# scraptcha.net
KiCad netlist of a schematic drawn in EAGLE
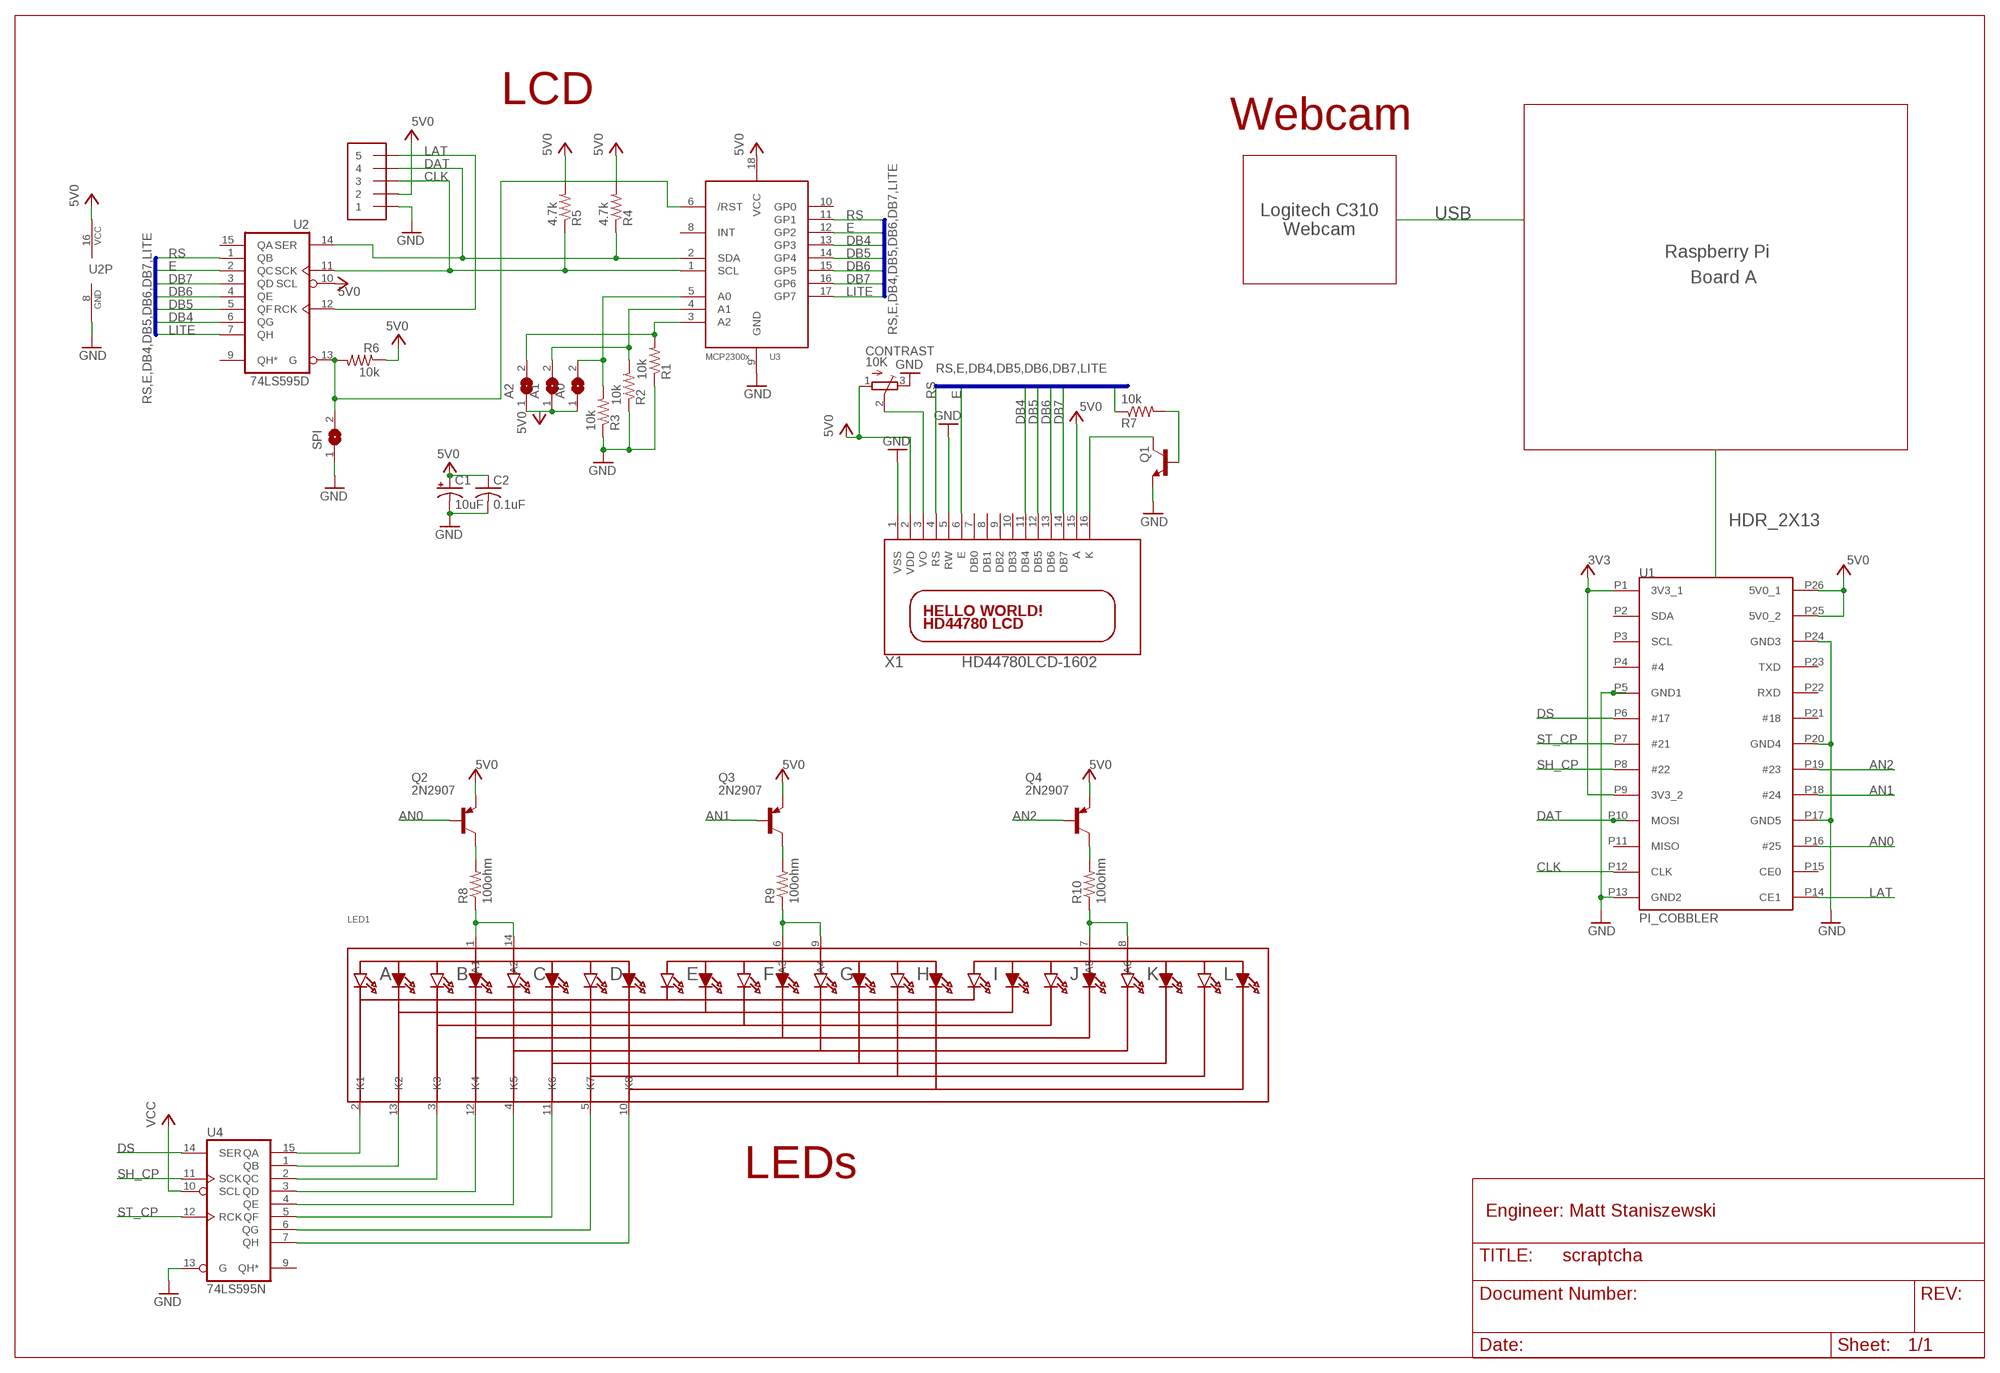
[diagram p0: schematic, sheet 1]

(export (version "E")
  (design (tool "Eeschema 10.0.6"))
  (components
    (comp (ref "A0") (value "SJ") (footprint "eagle-import:SJ") (libsource (lib "eagle-import") (part "SJ")))
    (comp (ref "A1") (value "SJ") (footprint "eagle-import:SJ") (libsource (lib "eagle-import") (part "SJ")))
    (comp (ref "A2") (value "SJ") (footprint "eagle-import:SJ") (libsource (lib "eagle-import") (part "SJ")))
    (comp (ref "C1")
      (value "10uF")
      (footprint "eagle-import:A_3216-18R")
      (libsource (lib "eagle-import") (part "CPOL-USA/3216-18R"))
    )
    (comp (ref "C2")
      (value "0.1uF")
      (footprint "eagle-import:C0805K")
      (libsource (lib "eagle-import") (part "C-USC0805K"))
    )
    (comp (ref "CONTRAST")
      (value "10K")
      (footprint "eagle-import:TC33X")
      (libsource (lib "eagle-import") (part "TRIMPOTTC33X"))
    )
    (comp (ref "J1")
      (value "1X5")
      (footprint "eagle-import:3.5MM-5P")
      (libsource (lib "eagle-import") (part "1X5"))
    )
    (comp (ref "LED1")
      (value "SEGMENT_12BAR_BICOLORAR12Z3010")
      (footprint "eagle-import:SEGMENT_BICOL_BL-AR12Z3010")
      (libsource (lib "eagle-import") (part "SEGMENT_12BAR_BICOLORAR12Z3010"))
    )
    (comp (ref "Q1")
      (value "MMBT2222ALT1-NPN-SOT23-BEC")
      (footprint "eagle-import:SOT23-BEC")
      (libsource (lib "eagle-import") (part "-NPN-SOT23-BECMMBT2222ALT1"))
    )
    (comp (ref "Q2")
      (value "2N2907")
      (footprint "eagle-import:TO92-EBC-OVAL")
      (libsource (lib "eagle-import") (part "2N2907"))
    )
    (comp (ref "Q3")
      (value "2N2907")
      (footprint "eagle-import:TO92-EBC-OVAL")
      (libsource (lib "eagle-import") (part "2N2907"))
    )
    (comp (ref "Q4")
      (value "2N2907")
      (footprint "eagle-import:TO92-EBC-OVAL")
      (libsource (lib "eagle-import") (part "2N2907"))
    )
    (comp (ref "R1")
      (value "10k")
      (footprint "eagle-import:R0805")
      (libsource (lib "eagle-import") (part "R-US_R0805"))
    )
    (comp (ref "R2")
      (value "10k")
      (footprint "eagle-import:R0805")
      (libsource (lib "eagle-import") (part "R-US_R0805"))
    )
    (comp (ref "R3")
      (value "10k")
      (footprint "eagle-import:R0805")
      (libsource (lib "eagle-import") (part "R-US_R0805"))
    )
    (comp (ref "R4")
      (value "4.7k")
      (footprint "eagle-import:R0805")
      (libsource (lib "eagle-import") (part "R-US_R0805"))
    )
    (comp (ref "R5")
      (value "4.7k")
      (footprint "eagle-import:R0805")
      (libsource (lib "eagle-import") (part "R-US_R0805"))
    )
    (comp (ref "R6")
      (value "10k")
      (footprint "eagle-import:R0805")
      (libsource (lib "eagle-import") (part "R-US_R0805"))
    )
    (comp (ref "R7")
      (value "10k")
      (footprint "eagle-import:R0805")
      (libsource (lib "eagle-import") (part "R-US_R0805"))
    )
    (comp (ref "R8")
      (value "100ohm")
      (footprint "eagle-import:0204_5")
      (libsource (lib "eagle-import") (part "R-US_0204/5"))
    )
    (comp (ref "R9")
      (value "100ohm")
      (footprint "eagle-import:0204_5")
      (libsource (lib "eagle-import") (part "R-US_0204/5"))
    )
    (comp (ref "R10")
      (value "100ohm")
      (footprint "eagle-import:0204_5")
      (libsource (lib "eagle-import") (part "R-US_0204/5"))
    )
    (comp (ref "SPI") (value "SJ") (footprint "eagle-import:SJ") (libsource (lib "eagle-import") (part "SJ")))
    (comp (ref "U1")
      (value "PI_COBBLER")
      (footprint "eagle-import:2X13_HDR")
      (libsource (lib "eagle-import") (part "PI_COBBLER"))
    )
    (comp (ref "U2")
      (value "74LS595D")
      (footprint "eagle-import:SO16")
      (libsource (lib "eagle-import") (part "74595DLS"))
    )
    (comp (ref "U3")
      (value "MCP2300X/SO")
      (footprint "eagle-import:SO18W")
      (libsource (lib "eagle-import") (part "MCP2300X/SO"))
    )
    (comp (ref "U4")
      (value "74LS595N")
      (footprint "eagle-import:DIL16")
      (libsource (lib "eagle-import") (part "74595NLS"))
    )
    (comp (ref "X1")
      (value "HD44780LCD-1602")
      (footprint "eagle-import:LCD1602")
      (libsource (lib "eagle-import") (part "HD44780LCD-1602"))
    )
  )
  (nets
    (net (code "1") (name "/AN0") (class "Default")
      (node (ref "Q2") (pin "B") (pinfunction "B_B") (pintype "passive"))
      (node (ref "U1") (pin "P16") (pinfunction "#25_P16") (pintype "bidirectional"))
    )
    (net (code "2") (name "/AN1") (class "Default")
      (node (ref "Q3") (pin "B") (pinfunction "B_B") (pintype "passive"))
      (node (ref "U1") (pin "P18") (pinfunction "#24_P18") (pintype "bidirectional"))
    )
    (net (code "3") (name "/AN2") (class "Default")
      (node (ref "Q4") (pin "B") (pinfunction "B_B") (pintype "passive"))
      (node (ref "U1") (pin "P19") (pinfunction "#23_P19") (pintype "bidirectional"))
    )
    (net (code "4") (name "/CLK") (class "Default")
      (node (ref "J1") (pin "3") (pinfunction "3_3") (pintype "passive"))
      (node (ref "R5") (pin "1") (pinfunction "1_1") (pintype "passive"))
      (node (ref "U1") (pin "P12") (pinfunction "CLK_P12") (pintype "bidirectional"))
      (node (ref "U2") (pin "11") (pinfunction "SCK_11") (pintype "input"))
      (node (ref "U3") (pin "1") (pinfunction "SCL_1") (pintype "bidirectional"))
    )
    (net (code "5") (name "/DAT") (class "Default")
      (node (ref "J1") (pin "4") (pinfunction "4_4") (pintype "passive"))
      (node (ref "R4") (pin "1") (pinfunction "1_1") (pintype "passive"))
      (node (ref "U1") (pin "P10") (pinfunction "MOSI_P10") (pintype "bidirectional"))
      (node (ref "U2") (pin "14") (pinfunction "SER_14") (pintype "input"))
      (node (ref "U3") (pin "2") (pinfunction "SDA_2") (pintype "bidirectional"))
    )
    (net (code "6") (name "/DB4") (class "Default")
      (node (ref "U2") (pin "6") (pinfunction "QG_6") (pintype "tri_state"))
      (node (ref "U3") (pin "13") (pinfunction "GP3_13") (pintype "bidirectional"))
      (node (ref "X1") (pin "11") (pinfunction "DB4_11") (pintype "bidirectional"))
    )
    (net (code "7") (name "/DB5") (class "Default")
      (node (ref "U2") (pin "5") (pinfunction "QF_5") (pintype "tri_state"))
      (node (ref "U3") (pin "14") (pinfunction "GP4_14") (pintype "bidirectional"))
      (node (ref "X1") (pin "12") (pinfunction "DB5_12") (pintype "bidirectional"))
    )
    (net (code "8") (name "/DB6") (class "Default")
      (node (ref "U2") (pin "4") (pinfunction "QE_4") (pintype "tri_state"))
      (node (ref "U3") (pin "15") (pinfunction "GP5_15") (pintype "bidirectional"))
      (node (ref "X1") (pin "13") (pinfunction "DB6_13") (pintype "bidirectional"))
    )
    (net (code "9") (name "/DB7") (class "Default")
      (node (ref "U2") (pin "3") (pinfunction "QD_3") (pintype "tri_state"))
      (node (ref "U3") (pin "16") (pinfunction "GP6_16") (pintype "bidirectional"))
      (node (ref "X1") (pin "14") (pinfunction "DB7_14") (pintype "bidirectional"))
    )
    (net (code "10") (name "/DS") (class "Default")
      (node (ref "U1") (pin "P6") (pinfunction "#17_P6") (pintype "bidirectional"))
      (node (ref "U4") (pin "14") (pinfunction "SER_14") (pintype "input"))
    )
    (net (code "11") (name "/E") (class "Default")
      (node (ref "U2") (pin "2") (pinfunction "QC_2") (pintype "tri_state"))
      (node (ref "U3") (pin "12") (pinfunction "GP2_12") (pintype "bidirectional"))
      (node (ref "X1") (pin "6") (pinfunction "E_6") (pintype "input"))
    )
    (net (code "13") (name "/LAT") (class "Default")
      (node (ref "J1") (pin "5") (pinfunction "5_5") (pintype "passive"))
      (node (ref "U1") (pin "P14") (pinfunction "CE1_P14") (pintype "bidirectional"))
      (node (ref "U2") (pin "12") (pinfunction "RCK_12") (pintype "input"))
    )
    (net (code "14") (name "/LITE") (class "Default")
      (node (ref "R7") (pin "1") (pinfunction "1_1") (pintype "passive"))
      (node (ref "U2") (pin "7") (pinfunction "QH_7") (pintype "tri_state"))
      (node (ref "U3") (pin "17") (pinfunction "GP7_17") (pintype "bidirectional"))
    )
    (net (code "15") (name "/RS") (class "Default")
      (node (ref "U2") (pin "1") (pinfunction "QB_1") (pintype "tri_state"))
      (node (ref "U3") (pin "11") (pinfunction "GP1_11") (pintype "bidirectional"))
      (node (ref "X1") (pin "4") (pinfunction "RS_4") (pintype "input"))
    )
    (net (code "16") (name "/SH_CP") (class "Default")
      (node (ref "U1") (pin "P8") (pinfunction "#22_P8") (pintype "bidirectional"))
      (node (ref "U4") (pin "11") (pinfunction "SCK_11") (pintype "input"))
    )
    (net (code "17") (name "/ST_CP") (class "Default")
      (node (ref "U1") (pin "P7") (pinfunction "#21_P7") (pintype "bidirectional"))
      (node (ref "U4") (pin "12") (pinfunction "RCK_12") (pintype "input"))
    )
    (net (code "20") (name "3V3") (class "Default")
      (node (ref "A0") (pin "1") (pinfunction "1_1") (pintype "passive"))
      (node (ref "A1") (pin "1") (pinfunction "1_1") (pintype "passive"))
      (node (ref "A2") (pin "1") (pinfunction "1_1") (pintype "passive"))
      (node (ref "C1") (pin "+") (pinfunction "+_+") (pintype "passive"))
      (node (ref "C2") (pin "1") (pinfunction "1_1") (pintype "passive"))
      (node (ref "CONTRAST") (pin "1") (pinfunction "A_1") (pintype "passive"))
      (node (ref "J1") (pin "2") (pinfunction "2_2") (pintype "passive"))
      (node (ref "Q2") (pin "E") (pinfunction "E_E") (pintype "passive"))
      (node (ref "Q3") (pin "E") (pinfunction "E_E") (pintype "passive"))
      (node (ref "Q4") (pin "E") (pinfunction "E_E") (pintype "passive"))
      (node (ref "R4") (pin "2") (pinfunction "2_2") (pintype "passive"))
      (node (ref "R5") (pin "2") (pinfunction "2_2") (pintype "passive"))
      (node (ref "R6") (pin "1") (pinfunction "1_1") (pintype "passive"))
      (node (ref "U1") (pin "P1") (pinfunction "3V3_1_P1") (pintype "bidirectional"))
      (node (ref "U1") (pin "P25") (pinfunction "5V0_2_P25") (pintype "bidirectional"))
      (node (ref "U1") (pin "P26") (pinfunction "5V0_1_P26") (pintype "bidirectional"))
      (node (ref "U1") (pin "P9") (pinfunction "3V3_2_P9") (pintype "bidirectional"))
      (node (ref "U2") (pin "10") (pinfunction "SCL_10") (pintype "input"))
      (node (ref "U2") (pin "16") (pinfunction "VCC_16") (pintype "power_in"))
      (node (ref "U3") (pin "18") (pinfunction "VCC_18") (pintype "power_in"))
      (node (ref "U4") (pin "10") (pinfunction "SCL_10") (pintype "input"))
      (node (ref "X1") (pin "15") (pinfunction "A_15") (pintype "input"))
      (node (ref "X1") (pin "2") (pinfunction "VDD_2") (pintype "power_in"))
    )
    (net (code "21") (name "GND") (class "Default")
      (node (ref "C1") (pin "-") (pinfunction "-_-") (pintype "passive"))
      (node (ref "C2") (pin "2") (pinfunction "2_2") (pintype "passive"))
      (node (ref "CONTRAST") (pin "3") (pinfunction "E_3") (pintype "passive"))
      (node (ref "J1") (pin "1") (pinfunction "1_1") (pintype "passive"))
      (node (ref "Q1") (pin "E") (pinfunction "E_E") (pintype "passive"))
      (node (ref "R1") (pin "1") (pinfunction "1_1") (pintype "passive"))
      (node (ref "R2") (pin "1") (pinfunction "1_1") (pintype "passive"))
      (node (ref "R3") (pin "1") (pinfunction "1_1") (pintype "passive"))
      (node (ref "SPI") (pin "1") (pinfunction "1_1") (pintype "passive"))
      (node (ref "U1") (pin "P13") (pinfunction "GND2_P13") (pintype "bidirectional"))
      (node (ref "U1") (pin "P17") (pinfunction "GND5_P17") (pintype "bidirectional"))
      (node (ref "U1") (pin "P20") (pinfunction "GND4_P20") (pintype "bidirectional"))
      (node (ref "U1") (pin "P24") (pinfunction "GND3_P24") (pintype "bidirectional"))
      (node (ref "U1") (pin "P5") (pinfunction "GND1_P5") (pintype "bidirectional"))
      (node (ref "U2") (pin "8") (pinfunction "GND_8") (pintype "power_in"))
      (node (ref "U3") (pin "9") (pinfunction "GND_9") (pintype "power_in"))
      (node (ref "U4") (pin "13") (pinfunction "G_13") (pintype "input"))
      (node (ref "X1") (pin "1") (pinfunction "VSS_1") (pintype "power_in"))
      (node (ref "X1") (pin "5") (pinfunction "RW_5") (pintype "input"))
    )
    (net (code "22") (name "Net-(CONTRAST-S)") (class "Default")
      (node (ref "CONTRAST") (pin "2") (pinfunction "S_2") (pintype "passive"))
      (node (ref "X1") (pin "3") (pinfunction "VO_3") (pintype "input"))
    )
    (net (code "23") (name "Net-(LED1-A1)") (class "Default")
      (node (ref "LED1") (pin "1") (pinfunction "A1_1") (pintype "bidirectional"))
      (node (ref "LED1") (pin "14") (pinfunction "A2_14") (pintype "bidirectional"))
      (node (ref "R8") (pin "1") (pinfunction "1_1") (pintype "passive"))
    )
    (net (code "24") (name "Net-(LED1-A3)") (class "Default")
      (node (ref "LED1") (pin "6") (pinfunction "A3_6") (pintype "bidirectional"))
      (node (ref "LED1") (pin "9") (pinfunction "A4_9") (pintype "bidirectional"))
      (node (ref "R9") (pin "1") (pinfunction "1_1") (pintype "passive"))
    )
    (net (code "25") (name "Net-(LED1-A5)") (class "Default")
      (node (ref "LED1") (pin "7") (pinfunction "A5_7") (pintype "bidirectional"))
      (node (ref "LED1") (pin "8") (pinfunction "A6_8") (pintype "bidirectional"))
      (node (ref "R10") (pin "1") (pinfunction "1_1") (pintype "passive"))
    )
    (net (code "26") (name "Net-(LED1-K1)") (class "Default")
      (node (ref "LED1") (pin "2") (pinfunction "K1_2") (pintype "bidirectional"))
      (node (ref "U4") (pin "15") (pinfunction "QA_15") (pintype "tri_state"))
    )
    (net (code "27") (name "Net-(LED1-K2)") (class "Default")
      (node (ref "LED1") (pin "13") (pinfunction "K2_13") (pintype "bidirectional"))
      (node (ref "U4") (pin "1") (pinfunction "QB_1") (pintype "tri_state"))
    )
    (net (code "28") (name "Net-(LED1-K3)") (class "Default")
      (node (ref "LED1") (pin "3") (pinfunction "K3_3") (pintype "bidirectional"))
      (node (ref "U4") (pin "2") (pinfunction "QC_2") (pintype "tri_state"))
    )
    (net (code "29") (name "Net-(LED1-K4)") (class "Default")
      (node (ref "LED1") (pin "12") (pinfunction "K4_12") (pintype "bidirectional"))
      (node (ref "U4") (pin "3") (pinfunction "QD_3") (pintype "tri_state"))
    )
    (net (code "30") (name "Net-(LED1-K5)") (class "Default")
      (node (ref "LED1") (pin "4") (pinfunction "K5_4") (pintype "bidirectional"))
      (node (ref "U4") (pin "4") (pinfunction "QE_4") (pintype "tri_state"))
    )
    (net (code "31") (name "Net-(LED1-K6)") (class "Default")
      (node (ref "LED1") (pin "11") (pinfunction "K6_11") (pintype "bidirectional"))
      (node (ref "U4") (pin "5") (pinfunction "QF_5") (pintype "tri_state"))
    )
    (net (code "32") (name "Net-(LED1-K7)") (class "Default")
      (node (ref "LED1") (pin "5") (pinfunction "K7_5") (pintype "bidirectional"))
      (node (ref "U4") (pin "6") (pinfunction "QG_6") (pintype "tri_state"))
    )
    (net (code "33") (name "Net-(LED1-K8)") (class "Default")
      (node (ref "LED1") (pin "10") (pinfunction "K8_10") (pintype "bidirectional"))
      (node (ref "U4") (pin "7") (pinfunction "QH_7") (pintype "tri_state"))
    )
    (net (code "34") (name "Net-(Q1-PadB)") (class "Default")
      (node (ref "Q1") (pin "B") (pinfunction "B_B") (pintype "passive"))
      (node (ref "R7") (pin "2") (pinfunction "2_2") (pintype "passive"))
    )
    (net (code "35") (name "Net-(Q2-PadC)") (class "Default")
      (node (ref "Q2") (pin "C") (pinfunction "C_C") (pintype "passive"))
      (node (ref "R8") (pin "2") (pinfunction "2_2") (pintype "passive"))
    )
    (net (code "36") (name "Net-(Q3-PadC)") (class "Default")
      (node (ref "Q3") (pin "C") (pinfunction "C_C") (pintype "passive"))
      (node (ref "R9") (pin "2") (pinfunction "2_2") (pintype "passive"))
    )
    (net (code "37") (name "Net-(Q4-PadC)") (class "Default")
      (node (ref "Q4") (pin "C") (pinfunction "C_C") (pintype "passive"))
      (node (ref "R10") (pin "2") (pinfunction "2_2") (pintype "passive"))
    )
    (net (code "38") (name "Net-(U2A-G)") (class "Default")
      (node (ref "R6") (pin "2") (pinfunction "2_2") (pintype "passive"))
      (node (ref "SPI") (pin "2") (pinfunction "2_2") (pintype "passive"))
      (node (ref "U2") (pin "13") (pinfunction "G_13") (pintype "input"))
      (node (ref "U3") (pin "6") (pinfunction "/RST_6") (pintype "input"))
    )
    (net (code "39") (name "Net-(U3-A0)") (class "Default")
      (node (ref "A0") (pin "2") (pinfunction "2_2") (pintype "passive"))
      (node (ref "R3") (pin "2") (pinfunction "2_2") (pintype "passive"))
      (node (ref "U3") (pin "5") (pinfunction "A0_5") (pintype "input"))
    )
    (net (code "40") (name "Net-(U3-A1)") (class "Default")
      (node (ref "A1") (pin "2") (pinfunction "2_2") (pintype "passive"))
      (node (ref "R2") (pin "2") (pinfunction "2_2") (pintype "passive"))
      (node (ref "U3") (pin "4") (pinfunction "A1_4") (pintype "input"))
    )
    (net (code "41") (name "Net-(U3-A2)") (class "Default")
      (node (ref "A2") (pin "2") (pinfunction "2_2") (pintype "passive"))
      (node (ref "R1") (pin "2") (pinfunction "2_2") (pintype "passive"))
      (node (ref "U3") (pin "3") (pinfunction "A2_3") (pintype "input"))
    )
    (net (code "42") (name "Net-(X1-K)") (class "Default")
      (node (ref "Q1") (pin "C") (pinfunction "C_C") (pintype "passive"))
      (node (ref "X1") (pin "16") (pinfunction "K_16") (pintype "input"))
    )
    (net (code "43") (name "unconnected-(U1-#4-PadP4)") (class "Default")
      (node (ref "U1") (pin "P4") (pinfunction "#4_P4") (pintype "bidirectional"))
    )
    (net (code "44") (name "unconnected-(U1-#18-PadP21)") (class "Default")
      (node (ref "U1") (pin "P21") (pinfunction "#18_P21") (pintype "bidirectional"))
    )
    (net (code "45") (name "unconnected-(U1-CE0-PadP15)") (class "Default")
      (node (ref "U1") (pin "P15") (pinfunction "CE0_P15") (pintype "bidirectional"))
    )
    (net (code "46") (name "unconnected-(U1-MISO-PadP11)") (class "Default")
      (node (ref "U1") (pin "P11") (pinfunction "MISO_P11") (pintype "bidirectional"))
    )
    (net (code "47") (name "unconnected-(U1-RXD-PadP22)") (class "Default")
      (node (ref "U1") (pin "P22") (pinfunction "RXD_P22") (pintype "bidirectional"))
    )
    (net (code "48") (name "unconnected-(U1-SCL-PadP3)") (class "Default")
      (node (ref "U1") (pin "P3") (pinfunction "SCL_P3") (pintype "bidirectional"))
    )
    (net (code "49") (name "unconnected-(U1-SDA-PadP2)") (class "Default")
      (node (ref "U1") (pin "P2") (pinfunction "SDA_P2") (pintype "bidirectional"))
    )
    (net (code "50") (name "unconnected-(U1-TXD-PadP23)") (class "Default")
      (node (ref "U1") (pin "P23") (pinfunction "TXD_P23") (pintype "bidirectional"))
    )
    (net (code "51") (name "unconnected-(U2A-QA-Pad15)") (class "Default")
      (node (ref "U2") (pin "15") (pinfunction "QA_15") (pintype "tri_state"))
    )
    (net (code "52") (name "unconnected-(U2A-QH*-Pad9)") (class "Default")
      (node (ref "U2") (pin "9") (pinfunction "QH*_9") (pintype "tri_state"))
    )
    (net (code "53") (name "unconnected-(U3-GP0-Pad10)") (class "Default")
      (node (ref "U3") (pin "10") (pinfunction "GP0_10") (pintype "bidirectional"))
    )
    (net (code "54") (name "unconnected-(U3-INT-Pad8)") (class "Default")
      (node (ref "U3") (pin "8") (pinfunction "INT_8") (pintype "output"))
    )
    (net (code "55") (name "unconnected-(U4A-QH*-Pad9)") (class "Default")
      (node (ref "U4") (pin "9") (pinfunction "QH*_9") (pintype "tri_state"))
    )
    (net (code "56") (name "unconnected-(X1-DB0-Pad7)") (class "Default")
      (node (ref "X1") (pin "7") (pinfunction "DB0_7") (pintype "bidirectional"))
    )
    (net (code "57") (name "unconnected-(X1-DB1-Pad8)") (class "Default")
      (node (ref "X1") (pin "8") (pinfunction "DB1_8") (pintype "bidirectional"))
    )
    (net (code "58") (name "unconnected-(X1-DB2-Pad9)") (class "Default")
      (node (ref "X1") (pin "9") (pinfunction "DB2_9") (pintype "bidirectional"))
    )
    (net (code "59") (name "unconnected-(X1-DB3-Pad10)") (class "Default")
      (node (ref "X1") (pin "10") (pinfunction "DB3_10") (pintype "bidirectional"))
    )
  )
)
